# PWM_Block.net
KiCad netlist of a schematic drawn in EAGLE
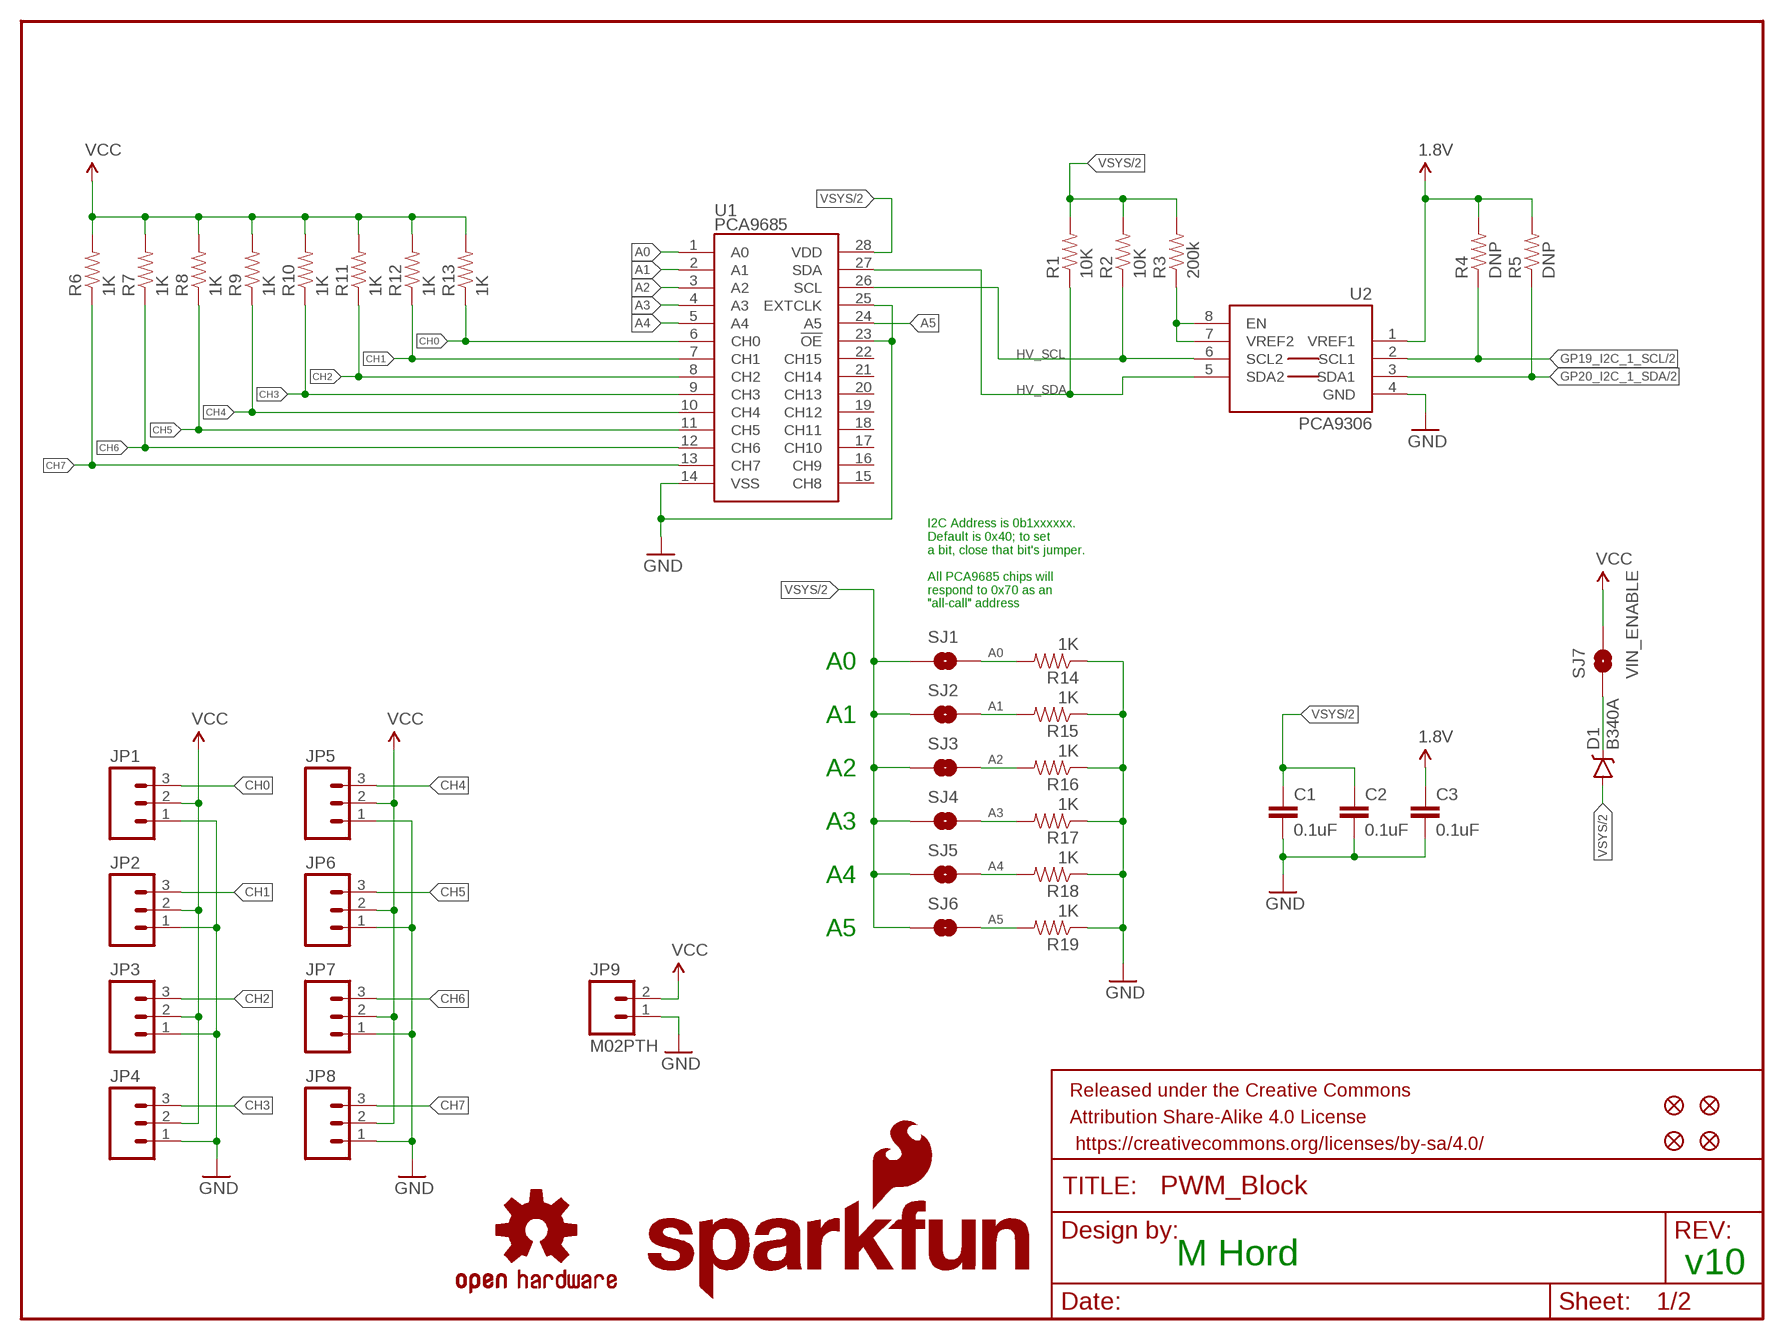
[diagram p0: schematic, sheet 1]
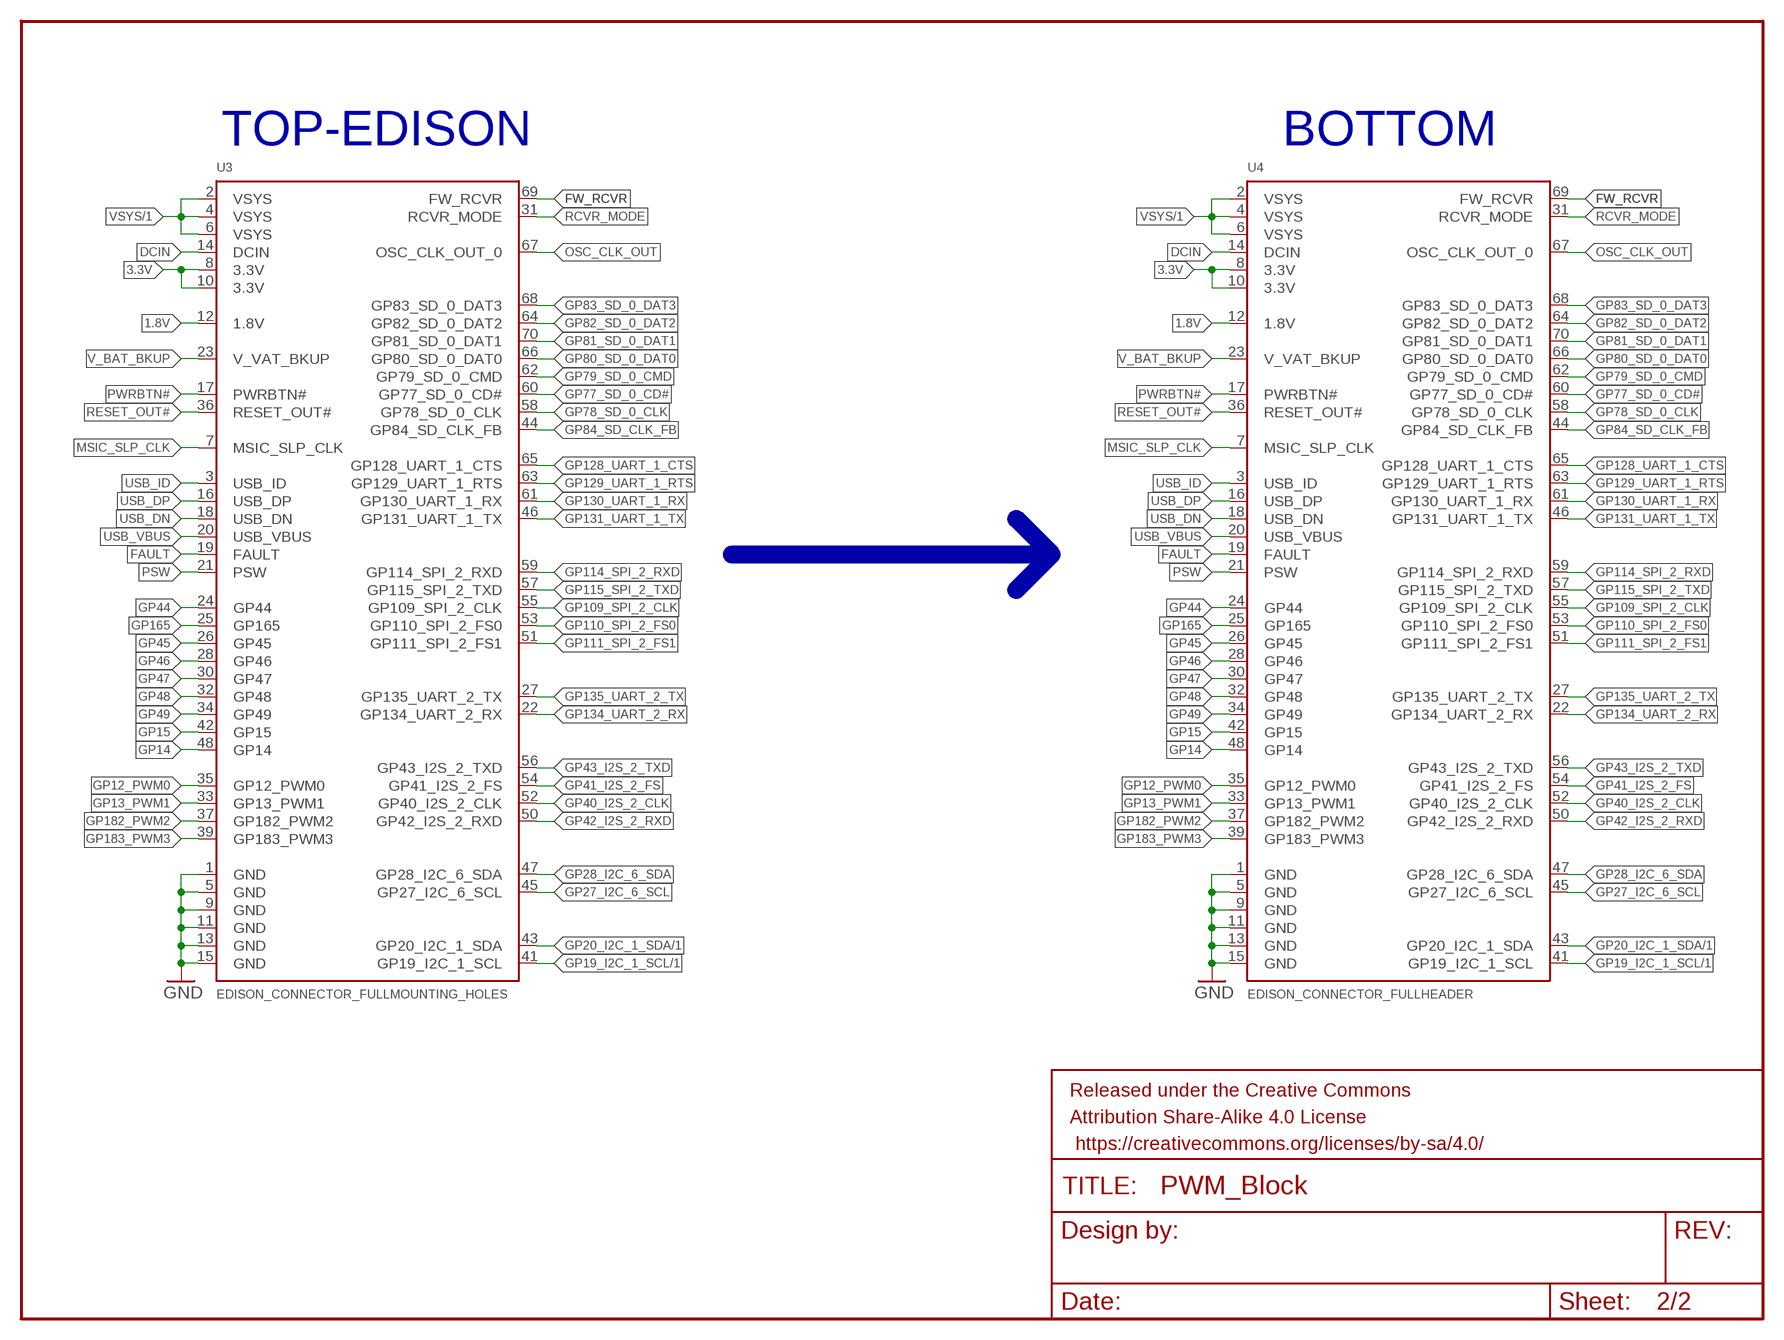
[diagram p1: schematic, sheet 2]

(export (version "E")
  (design (tool "Eeschema 10.0.6"))
  (components
    (comp (ref "FRAME2")
      (value "FRAME-LETTER")
      (footprint "eagle-import:CREATIVE_COMMONS")
      (libsource (lib "eagle-import") (part "FRAME-LETTER"))
    )
    (comp (ref "U3")
      (value "EDISON_CONNECTOR_FULLMOUNTING_HOLES")
      (footprint "eagle-import:EDISON_DAUGHTER")
      (libsource (lib "eagle-import") (part "EDISON_CONNECTOR_FULLMOUNTING_HOLES"))
    )
    (comp (ref "U4")
      (value "EDISON_CONNECTOR_FULLHEADER")
      (footprint "eagle-import:DF40C-70DP-0.4(51)")
      (libsource (lib "eagle-import") (part "EDISON_CONNECTOR_FULLHEADER"))
    )
    (comp (ref "C1")
      (value "0.1uF")
      (footprint "eagle-import:0603-CAP")
      (libsource (lib "eagle-import") (part "0.1UF-25V(+80/-20%)(0603)"))
    )
    (comp (ref "C2")
      (value "0.1uF")
      (footprint "eagle-import:0603-CAP")
      (libsource (lib "eagle-import") (part "0.1UF-25V(+80/-20%)(0603)"))
    )
    (comp (ref "C3")
      (value "0.1uF")
      (footprint "eagle-import:0603-CAP")
      (libsource (lib "eagle-import") (part "0.1UF-25V(+80/-20%)(0603)"))
    )
    (comp (ref "D1")
      (value "B340A")
      (footprint "eagle-import:SMA-DIODE")
      (libsource (lib "eagle-import") (part "DIODE-SCHOTTKY-B340A"))
    )
    (comp (ref "FID1")
      (value "FIDUCIAL1X2")
      (footprint "eagle-import:FIDUCIAL-1X2")
      (libsource (lib "eagle-import") (part "FIDUCIAL1X2"))
    )
    (comp (ref "FID2")
      (value "FIDUCIAL1X2")
      (footprint "eagle-import:FIDUCIAL-1X2")
      (libsource (lib "eagle-import") (part "FIDUCIAL1X2"))
    )
    (comp (ref "FID3")
      (value "FIDUCIAL1X2")
      (footprint "eagle-import:FIDUCIAL-1X2")
      (libsource (lib "eagle-import") (part "FIDUCIAL1X2"))
    )
    (comp (ref "FID4")
      (value "FIDUCIAL1X2")
      (footprint "eagle-import:FIDUCIAL-1X2")
      (libsource (lib "eagle-import") (part "FIDUCIAL1X2"))
    )
    (comp (ref "FRAME1")
      (value "FRAME-LETTER")
      (footprint "eagle-import:CREATIVE_COMMONS")
      (libsource (lib "eagle-import") (part "FRAME-LETTER"))
    )
    (comp (ref "JP1")
      (value "M03PTH")
      (footprint "eagle-import:1X03")
      (libsource (lib "eagle-import") (part "M03PTH"))
    )
    (comp (ref "JP2")
      (value "M03PTH")
      (footprint "eagle-import:1X03")
      (libsource (lib "eagle-import") (part "M03PTH"))
    )
    (comp (ref "JP3")
      (value "M03PTH")
      (footprint "eagle-import:1X03")
      (libsource (lib "eagle-import") (part "M03PTH"))
    )
    (comp (ref "JP4")
      (value "M03PTH")
      (footprint "eagle-import:1X03")
      (libsource (lib "eagle-import") (part "M03PTH"))
    )
    (comp (ref "JP5")
      (value "M03PTH")
      (footprint "eagle-import:1X03")
      (libsource (lib "eagle-import") (part "M03PTH"))
    )
    (comp (ref "JP6")
      (value "M03PTH")
      (footprint "eagle-import:1X03")
      (libsource (lib "eagle-import") (part "M03PTH"))
    )
    (comp (ref "JP7")
      (value "M03PTH")
      (footprint "eagle-import:1X03")
      (libsource (lib "eagle-import") (part "M03PTH"))
    )
    (comp (ref "JP8")
      (value "M03PTH")
      (footprint "eagle-import:1X03")
      (libsource (lib "eagle-import") (part "M03PTH"))
    )
    (comp (ref "JP9")
      (value "M02PTH")
      (footprint "eagle-import:1X02")
      (libsource (lib "eagle-import") (part "M02PTH"))
    )
    (comp (ref "LOGO1")
      (value "SFE_LOGO_NAME_FLAME.1_INCH")
      (footprint "eagle-import:SFE_LOGO_NAME_FLAME_.1")
      (libsource (lib "eagle-import") (part "SFE_LOGO_NAME_FLAME.1_INCH"))
    )
    (comp (ref "LOGO2")
      (value "OSHW-LOGOS")
      (footprint "eagle-import:OSHW-LOGO-S")
      (libsource (lib "eagle-import") (part "OSHW-LOGOS"))
    )
    (comp (ref "LOGO3")
      (value "SFE_LOGO_NAME_FLAME.1_INCH")
      (footprint "eagle-import:SFE_LOGO_NAME_FLAME_.1")
      (libsource (lib "eagle-import") (part "SFE_LOGO_NAME_FLAME.1_INCH"))
    )
    (comp (ref "LOGO4")
      (value "OSHW-LOGOS")
      (footprint "eagle-import:OSHW-LOGO-S")
      (libsource (lib "eagle-import") (part "OSHW-LOGOS"))
    )
    (comp (ref "R1")
      (value "10K")
      (footprint "eagle-import:0603-RES")
      (libsource (lib "eagle-import") (part "10KOHM1/10W1%(0603)0603"))
    )
    (comp (ref "R2")
      (value "10K")
      (footprint "eagle-import:0603-RES")
      (libsource (lib "eagle-import") (part "10KOHM1/10W1%(0603)0603"))
    )
    (comp (ref "R3")
      (value "200k")
      (footprint "eagle-import:0603-RES")
      (libsource (lib "eagle-import") (part "200KOHM1/10W1%(0603)200K"))
    )
    (comp (ref "R4")
      (value "DNP")
      (footprint "eagle-import:0603-RES")
      (libsource (lib "eagle-import") (part "2.2KOHM1/10W1%(0603)"))
    )
    (comp (ref "R5")
      (value "DNP")
      (footprint "eagle-import:0603-RES")
      (libsource (lib "eagle-import") (part "2.2KOHM1/10W1%(0603)"))
    )
    (comp (ref "R6")
      (value "1K")
      (footprint "eagle-import:0603-RES")
      (libsource (lib "eagle-import") (part "1KOHM1/10W1%(0603)"))
    )
    (comp (ref "R7")
      (value "1K")
      (footprint "eagle-import:0603-RES")
      (libsource (lib "eagle-import") (part "1KOHM1/10W1%(0603)"))
    )
    (comp (ref "R8")
      (value "1K")
      (footprint "eagle-import:0603-RES")
      (libsource (lib "eagle-import") (part "1KOHM1/10W1%(0603)"))
    )
    (comp (ref "R9")
      (value "1K")
      (footprint "eagle-import:0603-RES")
      (libsource (lib "eagle-import") (part "1KOHM1/10W1%(0603)"))
    )
    (comp (ref "R10")
      (value "1K")
      (footprint "eagle-import:0603-RES")
      (libsource (lib "eagle-import") (part "1KOHM1/10W1%(0603)"))
    )
    (comp (ref "R11")
      (value "1K")
      (footprint "eagle-import:0603-RES")
      (libsource (lib "eagle-import") (part "1KOHM1/10W1%(0603)"))
    )
    (comp (ref "R12")
      (value "1K")
      (footprint "eagle-import:0603-RES")
      (libsource (lib "eagle-import") (part "1KOHM1/10W1%(0603)"))
    )
    (comp (ref "R13")
      (value "1K")
      (footprint "eagle-import:0603-RES")
      (libsource (lib "eagle-import") (part "1KOHM1/10W1%(0603)"))
    )
    (comp (ref "R14")
      (value "1K")
      (footprint "eagle-import:0603-RES")
      (libsource (lib "eagle-import") (part "1KOHM1/10W1%(0603)"))
    )
    (comp (ref "R15")
      (value "1K")
      (footprint "eagle-import:0603-RES")
      (libsource (lib "eagle-import") (part "1KOHM1/10W1%(0603)"))
    )
    (comp (ref "R16")
      (value "1K")
      (footprint "eagle-import:0603-RES")
      (libsource (lib "eagle-import") (part "1KOHM1/10W1%(0603)"))
    )
    (comp (ref "R17")
      (value "1K")
      (footprint "eagle-import:0603-RES")
      (libsource (lib "eagle-import") (part "1KOHM1/10W1%(0603)"))
    )
    (comp (ref "R18")
      (value "1K")
      (footprint "eagle-import:0603-RES")
      (libsource (lib "eagle-import") (part "1KOHM1/10W1%(0603)"))
    )
    (comp (ref "R19")
      (value "1K")
      (footprint "eagle-import:0603-RES")
      (libsource (lib "eagle-import") (part "1KOHM1/10W1%(0603)"))
    )
    (comp (ref "SJ1")
      (value "JUMPER-PAD-2-NOYES_SILK")
      (footprint "eagle-import:PAD-JUMPER-2-NO_YES_SILK")
      (libsource (lib "eagle-import") (part "JUMPER-PAD-2-NOYES_SILK"))
    )
    (comp (ref "SJ2")
      (value "JUMPER-PAD-2-NOYES_SILK")
      (footprint "eagle-import:PAD-JUMPER-2-NO_YES_SILK")
      (libsource (lib "eagle-import") (part "JUMPER-PAD-2-NOYES_SILK"))
    )
    (comp (ref "SJ3")
      (value "JUMPER-PAD-2-NOYES_SILK")
      (footprint "eagle-import:PAD-JUMPER-2-NO_YES_SILK")
      (libsource (lib "eagle-import") (part "JUMPER-PAD-2-NOYES_SILK"))
    )
    (comp (ref "SJ4")
      (value "JUMPER-PAD-2-NOYES_SILK")
      (footprint "eagle-import:PAD-JUMPER-2-NO_YES_SILK")
      (libsource (lib "eagle-import") (part "JUMPER-PAD-2-NOYES_SILK"))
    )
    (comp (ref "SJ5")
      (value "JUMPER-PAD-2-NOYES_SILK")
      (footprint "eagle-import:PAD-JUMPER-2-NO_YES_SILK")
      (libsource (lib "eagle-import") (part "JUMPER-PAD-2-NOYES_SILK"))
    )
    (comp (ref "SJ6")
      (value "JUMPER-PAD-2-NOYES_SILK")
      (footprint "eagle-import:PAD-JUMPER-2-NO_YES_SILK")
      (libsource (lib "eagle-import") (part "JUMPER-PAD-2-NOYES_SILK"))
    )
    (comp (ref "SJ7")
      (value "VIN_ENABLE")
      (footprint "eagle-import:PAD-JUMPER-2-NO_YES_SILK")
      (libsource (lib "eagle-import") (part "JUMPER-PAD-2-NOYES_SILK"))
    )
    (comp (ref "U1")
      (value "PCA9685")
      (footprint "eagle-import:TSSOP-28_4MM")
      (libsource (lib "eagle-import") (part "PCA9685"))
    )
    (comp (ref "U2")
      (value "PCA9306")
      (footprint "eagle-import:PCA9306DC-1_1")
      (libsource (lib "eagle-import") (part "PCA9306PCA9306DC-1{colon}1"))
    )
  )
  (nets
    (net (code "1") (name "1.8V") (class "Default")
      (node (ref "C3") (pin "1") (pinfunction "1_1") (pintype "passive"))
      (node (ref "R4") (pin "2") (pinfunction "2_2") (pintype "passive"))
      (node (ref "R5") (pin "2") (pinfunction "2_2") (pintype "passive"))
      (node (ref "U2") (pin "1") (pinfunction "VREF1_1") (pintype "bidirectional"))
      (node (ref "U3") (pin "12") (pinfunction "1.8V_12") (pintype "bidirectional"))
      (node (ref "U4") (pin "12") (pinfunction "1.8V_12") (pintype "bidirectional"))
    )
    (net (code "2") (name "3.3V") (class "Default")
      (node (ref "U3") (pin "10") (pinfunction "3.3V_10") (pintype "bidirectional"))
      (node (ref "U3") (pin "8") (pinfunction "3.3V_8") (pintype "bidirectional"))
      (node (ref "U4") (pin "10") (pinfunction "3.3V_10") (pintype "bidirectional"))
      (node (ref "U4") (pin "8") (pinfunction "3.3V_8") (pintype "bidirectional"))
    )
    (net (code "3") (name "A0") (class "Default")
      (node (ref "R14") (pin "2") (pinfunction "2_2") (pintype "passive"))
      (node (ref "SJ1") (pin "2") (pinfunction "2_2") (pintype "passive"))
      (node (ref "U1") (pin "1") (pinfunction "A0_1") (pintype "bidirectional"))
    )
    (net (code "4") (name "A1") (class "Default")
      (node (ref "R15") (pin "2") (pinfunction "2_2") (pintype "passive"))
      (node (ref "SJ2") (pin "2") (pinfunction "2_2") (pintype "passive"))
      (node (ref "U1") (pin "2") (pinfunction "A1_2") (pintype "bidirectional"))
    )
    (net (code "5") (name "A2") (class "Default")
      (node (ref "R16") (pin "2") (pinfunction "2_2") (pintype "passive"))
      (node (ref "SJ3") (pin "2") (pinfunction "2_2") (pintype "passive"))
      (node (ref "U1") (pin "3") (pinfunction "A2_3") (pintype "bidirectional"))
    )
    (net (code "6") (name "A3") (class "Default")
      (node (ref "R17") (pin "2") (pinfunction "2_2") (pintype "passive"))
      (node (ref "SJ4") (pin "2") (pinfunction "2_2") (pintype "passive"))
      (node (ref "U1") (pin "4") (pinfunction "A3_4") (pintype "bidirectional"))
    )
    (net (code "7") (name "A4") (class "Default")
      (node (ref "R18") (pin "2") (pinfunction "2_2") (pintype "passive"))
      (node (ref "SJ5") (pin "2") (pinfunction "2_2") (pintype "passive"))
      (node (ref "U1") (pin "5") (pinfunction "A4_5") (pintype "bidirectional"))
    )
    (net (code "8") (name "A5") (class "Default")
      (node (ref "R19") (pin "2") (pinfunction "2_2") (pintype "passive"))
      (node (ref "SJ6") (pin "2") (pinfunction "2_2") (pintype "passive"))
      (node (ref "U1") (pin "24") (pinfunction "A5_24") (pintype "bidirectional"))
    )
    (net (code "9") (name "CH0") (class "Default")
      (node (ref "JP1") (pin "3") (pinfunction "3_3") (pintype "passive"))
      (node (ref "R13") (pin "1") (pinfunction "1_1") (pintype "passive"))
      (node (ref "U1") (pin "6") (pinfunction "CH0_6") (pintype "bidirectional"))
    )
    (net (code "10") (name "CH1") (class "Default")
      (node (ref "JP2") (pin "3") (pinfunction "3_3") (pintype "passive"))
      (node (ref "R12") (pin "1") (pinfunction "1_1") (pintype "passive"))
      (node (ref "U1") (pin "7") (pinfunction "CH1_7") (pintype "bidirectional"))
    )
    (net (code "11") (name "CH2") (class "Default")
      (node (ref "JP3") (pin "3") (pinfunction "3_3") (pintype "passive"))
      (node (ref "R11") (pin "1") (pinfunction "1_1") (pintype "passive"))
      (node (ref "U1") (pin "8") (pinfunction "CH2_8") (pintype "bidirectional"))
    )
    (net (code "12") (name "CH3") (class "Default")
      (node (ref "JP4") (pin "3") (pinfunction "3_3") (pintype "passive"))
      (node (ref "R10") (pin "1") (pinfunction "1_1") (pintype "passive"))
      (node (ref "U1") (pin "9") (pinfunction "CH3_9") (pintype "bidirectional"))
    )
    (net (code "13") (name "CH4") (class "Default")
      (node (ref "JP5") (pin "3") (pinfunction "3_3") (pintype "passive"))
      (node (ref "R9") (pin "1") (pinfunction "1_1") (pintype "passive"))
      (node (ref "U1") (pin "10") (pinfunction "CH4_10") (pintype "bidirectional"))
    )
    (net (code "14") (name "CH5") (class "Default")
      (node (ref "JP6") (pin "3") (pinfunction "3_3") (pintype "passive"))
      (node (ref "R8") (pin "1") (pinfunction "1_1") (pintype "passive"))
      (node (ref "U1") (pin "11") (pinfunction "CH5_11") (pintype "bidirectional"))
    )
    (net (code "15") (name "CH6") (class "Default")
      (node (ref "JP7") (pin "3") (pinfunction "3_3") (pintype "passive"))
      (node (ref "R7") (pin "1") (pinfunction "1_1") (pintype "passive"))
      (node (ref "U1") (pin "12") (pinfunction "CH6_12") (pintype "bidirectional"))
    )
    (net (code "16") (name "CH7") (class "Default")
      (node (ref "JP8") (pin "3") (pinfunction "3_3") (pintype "passive"))
      (node (ref "R6") (pin "1") (pinfunction "1_1") (pintype "passive"))
      (node (ref "U1") (pin "13") (pinfunction "CH7_13") (pintype "bidirectional"))
    )
    (net (code "17") (name "DCIN") (class "Default")
      (node (ref "U3") (pin "14") (pinfunction "DCIN_14") (pintype "bidirectional"))
      (node (ref "U4") (pin "14") (pinfunction "DCIN_14") (pintype "bidirectional"))
    )
    (net (code "18") (name "FAULT") (class "Default")
      (node (ref "U3") (pin "19") (pinfunction "FAULT_19") (pintype "bidirectional"))
      (node (ref "U4") (pin "19") (pinfunction "FAULT_19") (pintype "bidirectional"))
    )
    (net (code "19") (name "FW_RCVR") (class "Default")
      (node (ref "U3") (pin "69") (pinfunction "FW_RCVR_69") (pintype "bidirectional"))
      (node (ref "U4") (pin "69") (pinfunction "FW_RCVR_69") (pintype "bidirectional"))
    )
    (net (code "20") (name "GND") (class "Default")
      (node (ref "C1") (pin "2") (pinfunction "2_2") (pintype "passive"))
      (node (ref "C2") (pin "2") (pinfunction "2_2") (pintype "passive"))
      (node (ref "C3") (pin "2") (pinfunction "2_2") (pintype "passive"))
      (node (ref "JP1") (pin "1") (pinfunction "1_1") (pintype "passive"))
      (node (ref "JP2") (pin "1") (pinfunction "1_1") (pintype "passive"))
      (node (ref "JP3") (pin "1") (pinfunction "1_1") (pintype "passive"))
      (node (ref "JP4") (pin "1") (pinfunction "1_1") (pintype "passive"))
      (node (ref "JP5") (pin "1") (pinfunction "1_1") (pintype "passive"))
      (node (ref "JP6") (pin "1") (pinfunction "1_1") (pintype "passive"))
      (node (ref "JP7") (pin "1") (pinfunction "1_1") (pintype "passive"))
      (node (ref "JP8") (pin "1") (pinfunction "1_1") (pintype "passive"))
      (node (ref "JP9") (pin "1") (pinfunction "1_1") (pintype "passive"))
      (node (ref "R14") (pin "1") (pinfunction "1_1") (pintype "passive"))
      (node (ref "R15") (pin "1") (pinfunction "1_1") (pintype "passive"))
      (node (ref "R16") (pin "1") (pinfunction "1_1") (pintype "passive"))
      (node (ref "R17") (pin "1") (pinfunction "1_1") (pintype "passive"))
      (node (ref "R18") (pin "1") (pinfunction "1_1") (pintype "passive"))
      (node (ref "R19") (pin "1") (pinfunction "1_1") (pintype "passive"))
      (node (ref "U1") (pin "14") (pinfunction "VSS_14") (pintype "bidirectional"))
      (node (ref "U1") (pin "23") (pinfunction "~{OE}_23") (pintype "bidirectional"))
      (node (ref "U1") (pin "25") (pinfunction "EXTCLK_25") (pintype "bidirectional"))
      (node (ref "U2") (pin "4") (pinfunction "GND_4") (pintype "bidirectional"))
      (node (ref "U3") (pin "1") (pinfunction "GND_1") (pintype "bidirectional"))
      (node (ref "U3") (pin "11") (pinfunction "GND_11") (pintype "bidirectional"))
      (node (ref "U3") (pin "13") (pinfunction "GND_13") (pintype "bidirectional"))
      (node (ref "U3") (pin "15") (pinfunction "GND_15") (pintype "bidirectional"))
      (node (ref "U3") (pin "5") (pinfunction "GND_5") (pintype "bidirectional"))
      (node (ref "U3") (pin "9") (pinfunction "GND_9") (pintype "bidirectional"))
      (node (ref "U4") (pin "1") (pinfunction "GND_1") (pintype "bidirectional"))
      (node (ref "U4") (pin "11") (pinfunction "GND_11") (pintype "bidirectional"))
      (node (ref "U4") (pin "13") (pinfunction "GND_13") (pintype "bidirectional"))
      (node (ref "U4") (pin "15") (pinfunction "GND_15") (pintype "bidirectional"))
      (node (ref "U4") (pin "5") (pinfunction "GND_5") (pintype "bidirectional"))
      (node (ref "U4") (pin "9") (pinfunction "GND_9") (pintype "bidirectional"))
    )
    (net (code "21") (name "GP12_PWM0") (class "Default")
      (node (ref "U3") (pin "35") (pinfunction "GP12_PWM0_35") (pintype "bidirectional"))
      (node (ref "U4") (pin "35") (pinfunction "GP12_PWM0_35") (pintype "bidirectional"))
    )
    (net (code "22") (name "GP13_PWM1") (class "Default")
      (node (ref "U3") (pin "33") (pinfunction "GP13_PWM1_33") (pintype "bidirectional"))
      (node (ref "U4") (pin "33") (pinfunction "GP13_PWM1_33") (pintype "bidirectional"))
    )
    (net (code "23") (name "GP14") (class "Default")
      (node (ref "U3") (pin "48") (pinfunction "GP14_48") (pintype "bidirectional"))
      (node (ref "U4") (pin "48") (pinfunction "GP14_48") (pintype "bidirectional"))
    )
    (net (code "24") (name "GP15") (class "Default")
      (node (ref "U3") (pin "42") (pinfunction "GP15_42") (pintype "bidirectional"))
      (node (ref "U4") (pin "42") (pinfunction "GP15_42") (pintype "bidirectional"))
    )
    (net (code "25") (name "GP19_I2C_1_SCL") (class "Default")
      (node (ref "R4") (pin "1") (pinfunction "1_1") (pintype "passive"))
      (node (ref "U2") (pin "2") (pinfunction "SCL1_2") (pintype "bidirectional"))
      (node (ref "U3") (pin "41") (pinfunction "GP19_I2C_1_SCL_41") (pintype "bidirectional"))
      (node (ref "U4") (pin "41") (pinfunction "GP19_I2C_1_SCL_41") (pintype "bidirectional"))
    )
    (net (code "26") (name "GP20_I2C_1_SDA") (class "Default")
      (node (ref "R5") (pin "1") (pinfunction "1_1") (pintype "passive"))
      (node (ref "U2") (pin "3") (pinfunction "SDA1_3") (pintype "bidirectional"))
      (node (ref "U3") (pin "43") (pinfunction "GP20_I2C_1_SDA_43") (pintype "bidirectional"))
      (node (ref "U4") (pin "43") (pinfunction "GP20_I2C_1_SDA_43") (pintype "bidirectional"))
    )
    (net (code "27") (name "GP27_I2C_6_SCL") (class "Default")
      (node (ref "U3") (pin "45") (pinfunction "GP27_I2C_6_SCL_45") (pintype "bidirectional"))
      (node (ref "U4") (pin "45") (pinfunction "GP27_I2C_6_SCL_45") (pintype "bidirectional"))
    )
    (net (code "28") (name "GP28_I2C_6_SDA") (class "Default")
      (node (ref "U3") (pin "47") (pinfunction "GP28_I2C_6_SDA_47") (pintype "bidirectional"))
      (node (ref "U4") (pin "47") (pinfunction "GP28_I2C_6_SDA_47") (pintype "bidirectional"))
    )
    (net (code "29") (name "GP40_I2S_2_CLK") (class "Default")
      (node (ref "U3") (pin "52") (pinfunction "GP40_I2S_2_CLK_52") (pintype "bidirectional"))
      (node (ref "U4") (pin "52") (pinfunction "GP40_I2S_2_CLK_52") (pintype "bidirectional"))
    )
    (net (code "30") (name "GP41_I2S_2_FS") (class "Default")
      (node (ref "U3") (pin "54") (pinfunction "GP41_I2S_2_FS_54") (pintype "bidirectional"))
      (node (ref "U4") (pin "54") (pinfunction "GP41_I2S_2_FS_54") (pintype "bidirectional"))
    )
    (net (code "31") (name "GP42_I2S_2_RXD") (class "Default")
      (node (ref "U3") (pin "50") (pinfunction "GP42_I2S_2_RXD_50") (pintype "bidirectional"))
      (node (ref "U4") (pin "50") (pinfunction "GP42_I2S_2_RXD_50") (pintype "bidirectional"))
    )
    (net (code "32") (name "GP43_I2S_2_TXD") (class "Default")
      (node (ref "U3") (pin "56") (pinfunction "GP43_I2S_2_TXD_56") (pintype "bidirectional"))
      (node (ref "U4") (pin "56") (pinfunction "GP43_I2S_2_TXD_56") (pintype "bidirectional"))
    )
    (net (code "33") (name "GP44") (class "Default")
      (node (ref "U3") (pin "24") (pinfunction "GP44_24") (pintype "bidirectional"))
      (node (ref "U4") (pin "24") (pinfunction "GP44_24") (pintype "bidirectional"))
    )
    (net (code "34") (name "GP45") (class "Default")
      (node (ref "U3") (pin "26") (pinfunction "GP45_26") (pintype "bidirectional"))
      (node (ref "U4") (pin "26") (pinfunction "GP45_26") (pintype "bidirectional"))
    )
    (net (code "35") (name "GP46") (class "Default")
      (node (ref "U3") (pin "28") (pinfunction "GP46_28") (pintype "bidirectional"))
      (node (ref "U4") (pin "28") (pinfunction "GP46_28") (pintype "bidirectional"))
    )
    (net (code "36") (name "GP47") (class "Default")
      (node (ref "U3") (pin "30") (pinfunction "GP47_30") (pintype "bidirectional"))
      (node (ref "U4") (pin "30") (pinfunction "GP47_30") (pintype "bidirectional"))
    )
    (net (code "37") (name "GP48") (class "Default")
      (node (ref "U3") (pin "32") (pinfunction "GP48_32") (pintype "bidirectional"))
      (node (ref "U4") (pin "32") (pinfunction "GP48_32") (pintype "bidirectional"))
    )
    (net (code "38") (name "GP49") (class "Default")
      (node (ref "U3") (pin "34") (pinfunction "GP49_34") (pintype "bidirectional"))
      (node (ref "U4") (pin "34") (pinfunction "GP49_34") (pintype "bidirectional"))
    )
    (net (code "39") (name "GP77_SD_0_CD#") (class "Default")
      (node (ref "U3") (pin "60") (pinfunction "GP77_SD_0_CD#_60") (pintype "bidirectional"))
      (node (ref "U4") (pin "60") (pinfunction "GP77_SD_0_CD#_60") (pintype "bidirectional"))
    )
    (net (code "40") (name "GP78_SD_0_CLK") (class "Default")
      (node (ref "U3") (pin "58") (pinfunction "GP78_SD_0_CLK_58") (pintype "bidirectional"))
      (node (ref "U4") (pin "58") (pinfunction "GP78_SD_0_CLK_58") (pintype "bidirectional"))
    )
    (net (code "41") (name "GP79_SD_0_CMD") (class "Default")
      (node (ref "U3") (pin "62") (pinfunction "GP79_SD_0_CMD_62") (pintype "bidirectional"))
      (node (ref "U4") (pin "62") (pinfunction "GP79_SD_0_CMD_62") (pintype "bidirectional"))
    )
    (net (code "42") (name "GP80_SD_0_DAT0") (class "Default")
      (node (ref "U3") (pin "66") (pinfunction "GP80_SD_0_DAT0_66") (pintype "bidirectional"))
      (node (ref "U4") (pin "66") (pinfunction "GP80_SD_0_DAT0_66") (pintype "bidirectional"))
    )
    (net (code "43") (name "GP81_SD_0_DAT1") (class "Default")
      (node (ref "U3") (pin "70") (pinfunction "GP81_SD_0_DAT1_70") (pintype "bidirectional"))
      (node (ref "U4") (pin "70") (pinfunction "GP81_SD_0_DAT1_70") (pintype "bidirectional"))
    )
    (net (code "44") (name "GP82_SD_0_DAT2") (class "Default")
      (node (ref "U3") (pin "64") (pinfunction "GP82_SD_0_DAT2_64") (pintype "bidirectional"))
      (node (ref "U4") (pin "64") (pinfunction "GP82_SD_0_DAT2_64") (pintype "bidirectional"))
    )
    (net (code "45") (name "GP83_SD_0_DAT3") (class "Default")
      (node (ref "U3") (pin "68") (pinfunction "GP83_SD_0_DAT3_68") (pintype "bidirectional"))
      (node (ref "U4") (pin "68") (pinfunction "GP83_SD_0_DAT3_68") (pintype "bidirectional"))
    )
    (net (code "46") (name "GP84_SD_CLK_FB") (class "Default")
      (node (ref "U3") (pin "44") (pinfunction "GP84_SD_CLK_FB_44") (pintype "bidirectional"))
      (node (ref "U4") (pin "44") (pinfunction "GP84_SD_CLK_FB_44") (pintype "bidirectional"))
    )
    (net (code "47") (name "GP109_SPI_2_CLK") (class "Default")
      (node (ref "U3") (pin "55") (pinfunction "GP109_SPI_2_CLK_55") (pintype "bidirectional"))
      (node (ref "U4") (pin "55") (pinfunction "GP109_SPI_2_CLK_55") (pintype "bidirectional"))
    )
    (net (code "48") (name "GP110_SPI_2_FS0") (class "Default")
      (node (ref "U3") (pin "53") (pinfunction "GP110_SPI_2_FS0_53") (pintype "bidirectional"))
      (node (ref "U4") (pin "53") (pinfunction "GP110_SPI_2_FS0_53") (pintype "bidirectional"))
    )
    (net (code "49") (name "GP111_SPI_2_FS1") (class "Default")
      (node (ref "U3") (pin "51") (pinfunction "GP111_SPI_2_FS1_51") (pintype "bidirectional"))
      (node (ref "U4") (pin "51") (pinfunction "GP111_SPI_2_FS1_51") (pintype "bidirectional"))
    )
    (net (code "50") (name "GP114_SPI_2_RXD") (class "Default")
      (node (ref "U3") (pin "59") (pinfunction "GP114_SPI_2_RXD_59") (pintype "bidirectional"))
      (node (ref "U4") (pin "59") (pinfunction "GP114_SPI_2_RXD_59") (pintype "bidirectional"))
    )
    (net (code "51") (name "GP115_SPI_2_TXD") (class "Default")
      (node (ref "U3") (pin "57") (pinfunction "GP115_SPI_2_TXD_57") (pintype "bidirectional"))
      (node (ref "U4") (pin "57") (pinfunction "GP115_SPI_2_TXD_57") (pintype "bidirectional"))
    )
    (net (code "52") (name "GP128_UART_1_CTS") (class "Default")
      (node (ref "U3") (pin "65") (pinfunction "GP128_UART_1_CTS_65") (pintype "bidirectional"))
      (node (ref "U4") (pin "65") (pinfunction "GP128_UART_1_CTS_65") (pintype "bidirectional"))
    )
    (net (code "53") (name "GP129_UART_1_RTS") (class "Default")
      (node (ref "U3") (pin "63") (pinfunction "GP129_UART_1_RTS_63") (pintype "bidirectional"))
      (node (ref "U4") (pin "63") (pinfunction "GP129_UART_1_RTS_63") (pintype "bidirectional"))
    )
    (net (code "54") (name "GP130_UART_1_RX") (class "Default")
      (node (ref "U3") (pin "61") (pinfunction "GP130_UART_1_RX_61") (pintype "bidirectional"))
      (node (ref "U4") (pin "61") (pinfunction "GP130_UART_1_RX_61") (pintype "bidirectional"))
    )
    (net (code "55") (name "GP131_UART_1_TX") (class "Default")
      (node (ref "U3") (pin "46") (pinfunction "GP131_UART_1_TX_46") (pintype "bidirectional"))
      (node (ref "U4") (pin "46") (pinfunction "GP131_UART_1_TX_46") (pintype "bidirectional"))
    )
    (net (code "56") (name "GP134_UART_2_RX") (class "Default")
      (node (ref "U3") (pin "22") (pinfunction "GP134_UART_2_RX_22") (pintype "bidirectional"))
      (node (ref "U4") (pin "22") (pinfunction "GP134_UART_2_RX_22") (pintype "bidirectional"))
    )
    (net (code "57") (name "GP135_UART_2_TX") (class "Default")
      (node (ref "U3") (pin "27") (pinfunction "GP135_UART_2_TX_27") (pintype "bidirectional"))
      (node (ref "U4") (pin "27") (pinfunction "GP135_UART_2_TX_27") (pintype "bidirectional"))
    )
    (net (code "58") (name "GP165") (class "Default")
      (node (ref "U3") (pin "25") (pinfunction "GP165_25") (pintype "bidirectional"))
      (node (ref "U4") (pin "25") (pinfunction "GP165_25") (pintype "bidirectional"))
    )
    (net (code "59") (name "GP182_PWM2") (class "Default")
      (node (ref "U3") (pin "37") (pinfunction "GP182_PWM2_37") (pintype "bidirectional"))
      (node (ref "U4") (pin "37") (pinfunction "GP182_PWM2_37") (pintype "bidirectional"))
    )
    (net (code "60") (name "GP183_PWM3") (class "Default")
      (node (ref "U3") (pin "39") (pinfunction "GP183_PWM3_39") (pintype "bidirectional"))
      (node (ref "U4") (pin "39") (pinfunction "GP183_PWM3_39") (pintype "bidirectional"))
    )
    (net (code "61") (name "HV_SCL") (class "Default")
      (node (ref "R2") (pin "1") (pinfunction "1_1") (pintype "passive"))
      (node (ref "U1") (pin "26") (pinfunction "SCL_26") (pintype "bidirectional"))
      (node (ref "U2") (pin "6") (pinfunction "SCL2_6") (pintype "bidirectional"))
    )
    (net (code "62") (name "HV_SDA") (class "Default")
      (node (ref "R1") (pin "1") (pinfunction "1_1") (pintype "passive"))
      (node (ref "U1") (pin "27") (pinfunction "SDA_27") (pintype "bidirectional"))
      (node (ref "U2") (pin "5") (pinfunction "SDA2_5") (pintype "bidirectional"))
    )
    (net (code "63") (name "MSIC_SLP_CLK") (class "Default")
      (node (ref "U3") (pin "7") (pinfunction "MSIC_SLP_CLK_7") (pintype "bidirectional"))
      (node (ref "U4") (pin "7") (pinfunction "MSIC_SLP_CLK_7") (pintype "bidirectional"))
    )
    (net (code "64") (name "Net-(D1-PadC)") (class "Default")
      (node (ref "D1") (pin "C") (pinfunction "C_C") (pintype "passive"))
      (node (ref "SJ7") (pin "1") (pinfunction "1_1") (pintype "passive"))
    )
    (net (code "65") (name "Net-(U2-EN)") (class "Default")
      (node (ref "R3") (pin "1") (pinfunction "1_1") (pintype "passive"))
      (node (ref "U2") (pin "7") (pinfunction "VREF2_7") (pintype "bidirectional"))
      (node (ref "U2") (pin "8") (pinfunction "EN_8") (pintype "bidirectional"))
    )
    (net (code "66") (name "OSC_CLK_OUT") (class "Default")
      (node (ref "U3") (pin "67") (pinfunction "OSC_CLK_OUT_0_67") (pintype "bidirectional"))
      (node (ref "U4") (pin "67") (pinfunction "OSC_CLK_OUT_0_67") (pintype "bidirectional"))
    )
    (net (code "67") (name "PSW") (class "Default")
      (node (ref "U3") (pin "21") (pinfunction "PSW_21") (pintype "bidirectional"))
      (node (ref "U4") (pin "21") (pinfunction "PSW_21") (pintype "bidirectional"))
    )
    (net (code "68") (name "PWRBTN#") (class "Default")
      (node (ref "U3") (pin "17") (pinfunction "PWRBTN#_17") (pintype "bidirectional"))
      (node (ref "U4") (pin "17") (pinfunction "PWRBTN#_17") (pintype "bidirectional"))
    )
    (net (code "69") (name "RCVR_MODE") (class "Default")
      (node (ref "U3") (pin "31") (pinfunction "RCVR_MODE_31") (pintype "bidirectional"))
      (node (ref "U4") (pin "31") (pinfunction "RCVR_MODE_31") (pintype "bidirectional"))
    )
    (net (code "70") (name "RESET_OUT#") (class "Default")
      (node (ref "U3") (pin "36") (pinfunction "RESET_OUT#_36") (pintype "bidirectional"))
      (node (ref "U4") (pin "36") (pinfunction "RESET_OUT#_36") (pintype "bidirectional"))
    )
    (net (code "71") (name "USB_DN") (class "Default")
      (node (ref "U3") (pin "18") (pinfunction "USB_DN_18") (pintype "bidirectional"))
      (node (ref "U4") (pin "18") (pinfunction "USB_DN_18") (pintype "bidirectional"))
    )
    (net (code "72") (name "USB_DP") (class "Default")
      (node (ref "U3") (pin "16") (pinfunction "USB_DP_16") (pintype "bidirectional"))
      (node (ref "U4") (pin "16") (pinfunction "USB_DP_16") (pintype "bidirectional"))
    )
    (net (code "73") (name "USB_ID") (class "Default")
      (node (ref "U3") (pin "3") (pinfunction "USB_ID_3") (pintype "bidirectional"))
      (node (ref "U4") (pin "3") (pinfunction "USB_ID_3") (pintype "bidirectional"))
    )
    (net (code "74") (name "USB_VBUS") (class "Default")
      (node (ref "U3") (pin "20") (pinfunction "USB_VBUS_20") (pintype "bidirectional"))
      (node (ref "U4") (pin "20") (pinfunction "USB_VBUS_20") (pintype "bidirectional"))
    )
    (net (code "75") (name "VCC") (class "Default")
      (node (ref "JP1") (pin "2") (pinfunction "2_2") (pintype "passive"))
      (node (ref "JP2") (pin "2") (pinfunction "2_2") (pintype "passive"))
      (node (ref "JP3") (pin "2") (pinfunction "2_2") (pintype "passive"))
      (node (ref "JP4") (pin "2") (pinfunction "2_2") (pintype "passive"))
      (node (ref "JP5") (pin "2") (pinfunction "2_2") (pintype "passive"))
      (node (ref "JP6") (pin "2") (pinfunction "2_2") (pintype "passive"))
      (node (ref "JP7") (pin "2") (pinfunction "2_2") (pintype "passive"))
      (node (ref "JP8") (pin "2") (pinfunction "2_2") (pintype "passive"))
      (node (ref "JP9") (pin "2") (pinfunction "2_2") (pintype "passive"))
      (node (ref "R10") (pin "2") (pinfunction "2_2") (pintype "passive"))
      (node (ref "R11") (pin "2") (pinfunction "2_2") (pintype "passive"))
      (node (ref "R12") (pin "2") (pinfunction "2_2") (pintype "passive"))
      (node (ref "R13") (pin "2") (pinfunction "2_2") (pintype "passive"))
      (node (ref "R6") (pin "2") (pinfunction "2_2") (pintype "passive"))
      (node (ref "R7") (pin "2") (pinfunction "2_2") (pintype "passive"))
      (node (ref "R8") (pin "2") (pinfunction "2_2") (pintype "passive"))
      (node (ref "R9") (pin "2") (pinfunction "2_2") (pintype "passive"))
      (node (ref "SJ7") (pin "2") (pinfunction "2_2") (pintype "passive"))
    )
    (net (code "76") (name "VSYS") (class "Default")
      (node (ref "C1") (pin "1") (pinfunction "1_1") (pintype "passive"))
      (node (ref "C2") (pin "1") (pinfunction "1_1") (pintype "passive"))
      (node (ref "D1") (pin "A") (pinfunction "A_A") (pintype "passive"))
      (node (ref "R1") (pin "2") (pinfunction "2_2") (pintype "passive"))
      (node (ref "R2") (pin "2") (pinfunction "2_2") (pintype "passive"))
      (node (ref "R3") (pin "2") (pinfunction "2_2") (pintype "passive"))
      (node (ref "SJ1") (pin "1") (pinfunction "1_1") (pintype "passive"))
      (node (ref "SJ2") (pin "1") (pinfunction "1_1") (pintype "passive"))
      (node (ref "SJ3") (pin "1") (pinfunction "1_1") (pintype "passive"))
      (node (ref "SJ4") (pin "1") (pinfunction "1_1") (pintype "passive"))
      (node (ref "SJ5") (pin "1") (pinfunction "1_1") (pintype "passive"))
      (node (ref "SJ6") (pin "1") (pinfunction "1_1") (pintype "passive"))
      (node (ref "U1") (pin "28") (pinfunction "VDD_28") (pintype "bidirectional"))
      (node (ref "U3") (pin "2") (pinfunction "VSYS_2") (pintype "bidirectional"))
      (node (ref "U3") (pin "4") (pinfunction "VSYS_4") (pintype "bidirectional"))
      (node (ref "U3") (pin "6") (pinfunction "VSYS_6") (pintype "bidirectional"))
      (node (ref "U4") (pin "2") (pinfunction "VSYS_2") (pintype "bidirectional"))
      (node (ref "U4") (pin "4") (pinfunction "VSYS_4") (pintype "bidirectional"))
      (node (ref "U4") (pin "6") (pinfunction "VSYS_6") (pintype "bidirectional"))
    )
    (net (code "77") (name "V_BAT_BKUP") (class "Default")
      (node (ref "U3") (pin "23") (pinfunction "V_VAT_BKUP_23") (pintype "bidirectional"))
      (node (ref "U4") (pin "23") (pinfunction "V_VAT_BKUP_23") (pintype "bidirectional"))
    )
    (net (code "78") (name "unconnected-(U1-CH8-Pad15)") (class "Default")
      (node (ref "U1") (pin "15") (pinfunction "CH8_15") (pintype "bidirectional"))
    )
    (net (code "79") (name "unconnected-(U1-CH9-Pad16)") (class "Default")
      (node (ref "U1") (pin "16") (pinfunction "CH9_16") (pintype "bidirectional"))
    )
    (net (code "80") (name "unconnected-(U1-CH10-Pad17)") (class "Default")
      (node (ref "U1") (pin "17") (pinfunction "CH10_17") (pintype "bidirectional"))
    )
    (net (code "81") (name "unconnected-(U1-CH11-Pad18)") (class "Default")
      (node (ref "U1") (pin "18") (pinfunction "CH11_18") (pintype "bidirectional"))
    )
    (net (code "82") (name "unconnected-(U1-CH12-Pad19)") (class "Default")
      (node (ref "U1") (pin "19") (pinfunction "CH12_19") (pintype "bidirectional"))
    )
    (net (code "83") (name "unconnected-(U1-CH13-Pad20)") (class "Default")
      (node (ref "U1") (pin "20") (pinfunction "CH13_20") (pintype "bidirectional"))
    )
    (net (code "84") (name "unconnected-(U1-CH14-Pad21)") (class "Default")
      (node (ref "U1") (pin "21") (pinfunction "CH14_21") (pintype "bidirectional"))
    )
    (net (code "85") (name "unconnected-(U1-CH15-Pad22)") (class "Default")
      (node (ref "U1") (pin "22") (pinfunction "CH15_22") (pintype "bidirectional"))
    )
  )
)
